# Sheet1.net
KiCad netlist of a schematic drawn in Altium Designer
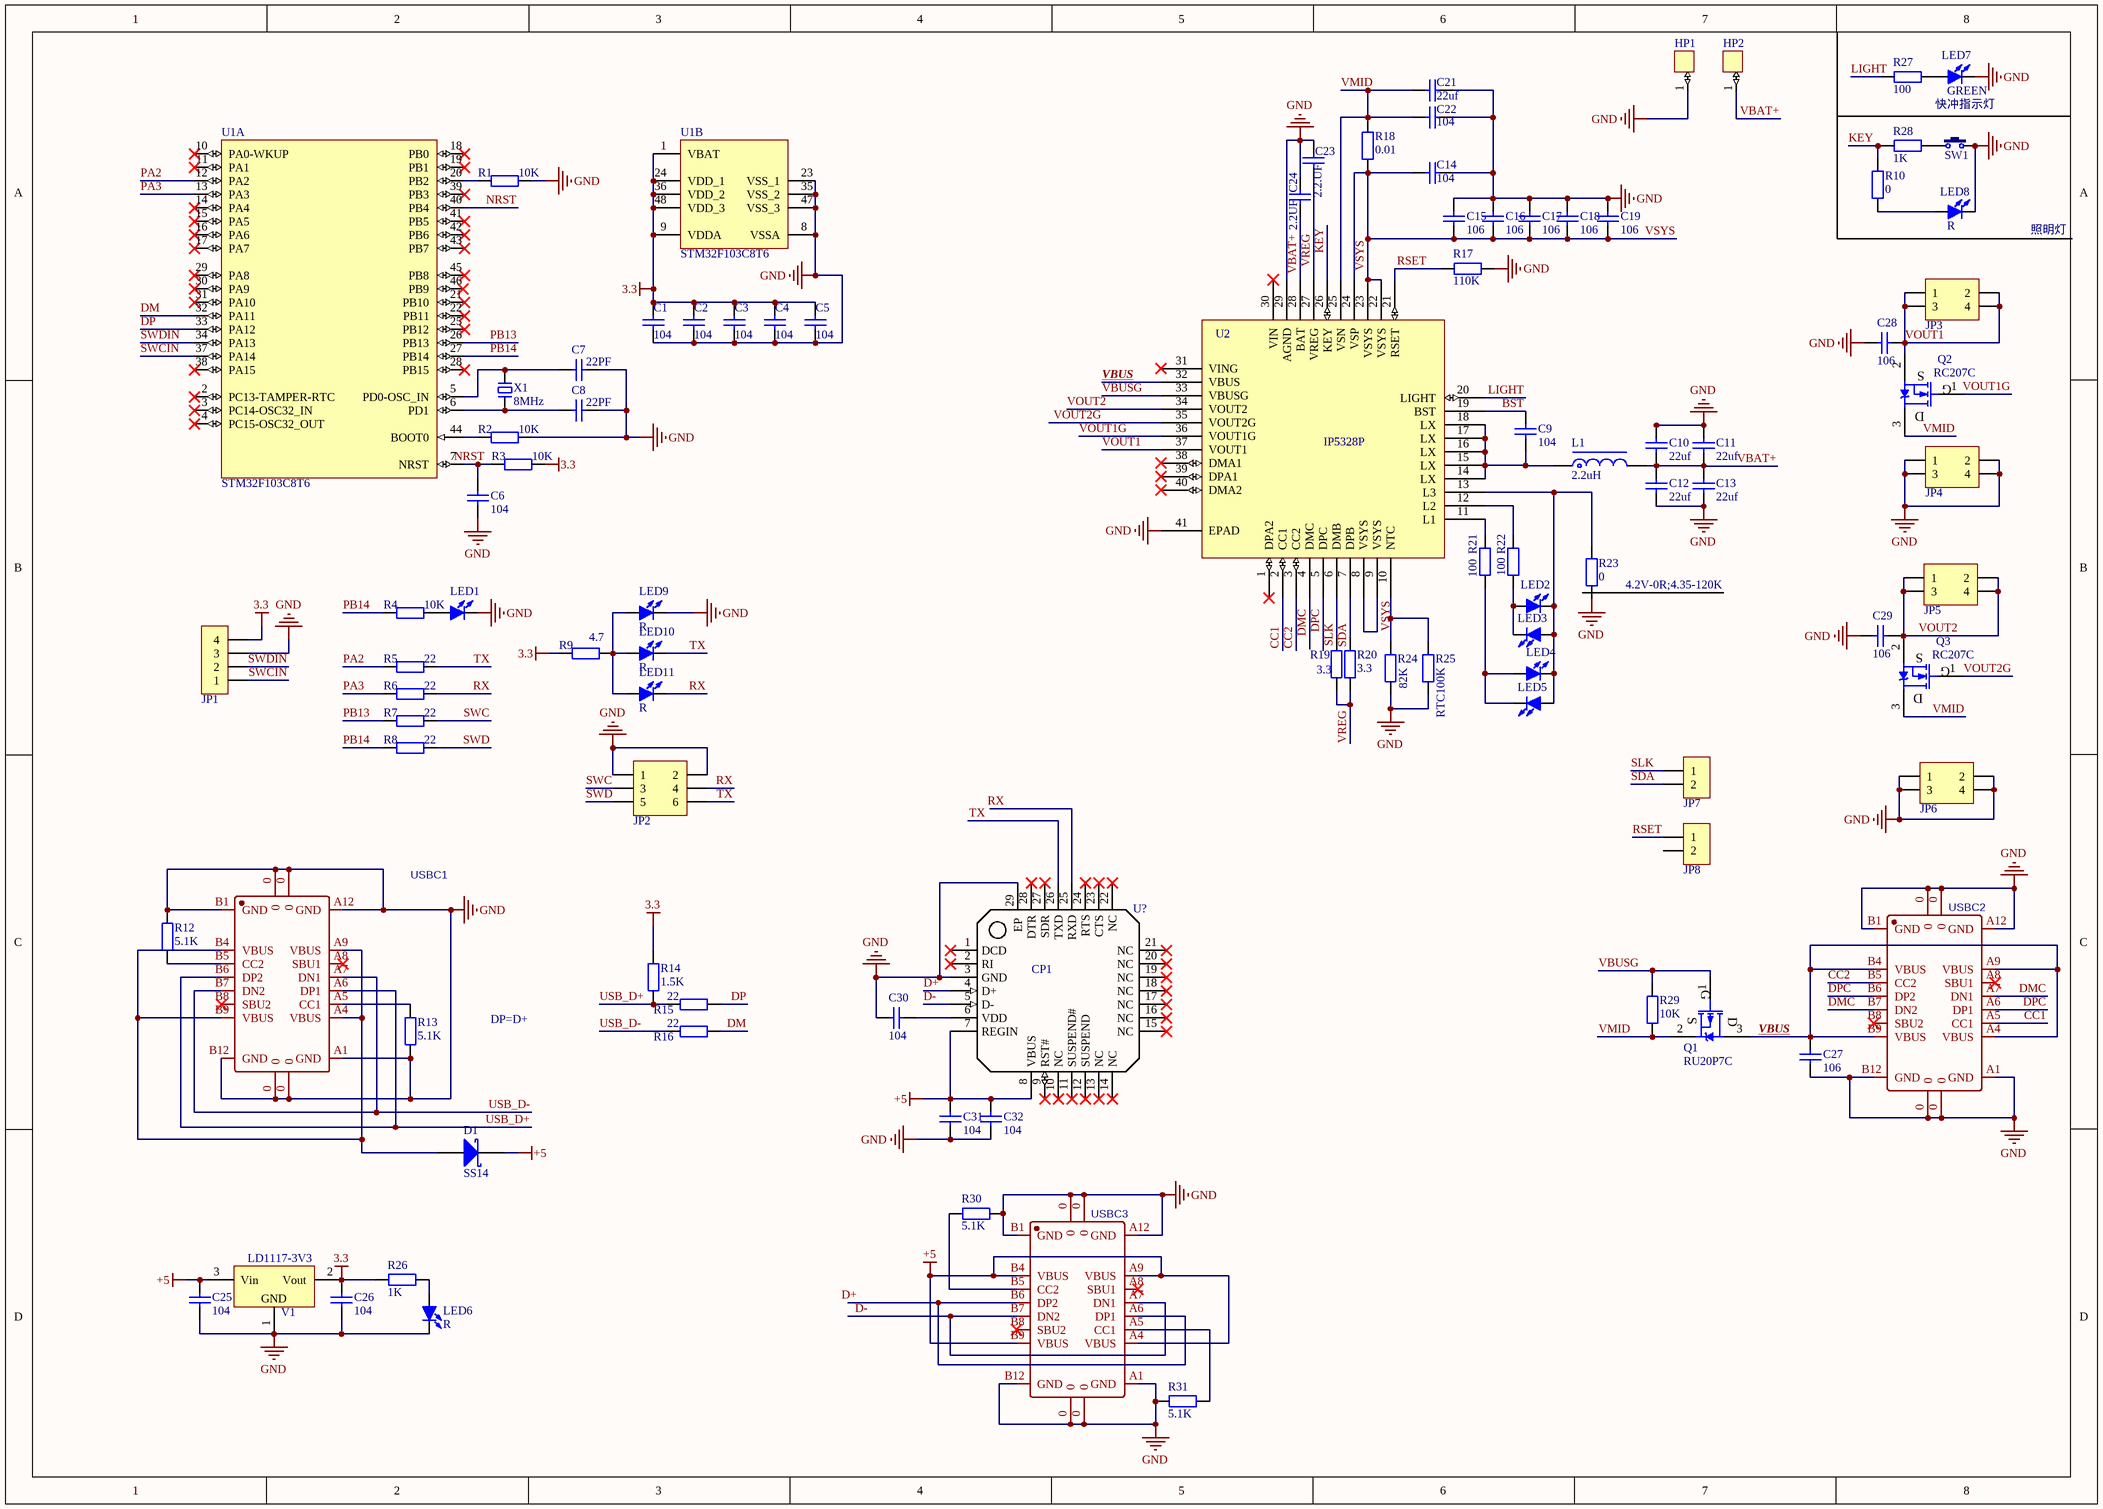
[diagram p0: Sheet1.SchDoc]

(export (version "E")
  (design (tool "Eeschema 10.0.6"))
  (components
    (comp (ref "C1")
      (value "104")
      (footprint "C 0603_L")
      (description "贴片电容")
      (libsource (lib "0.1 - 电阻-电容-电感") (part "C"))
    )
    (comp (ref "C2")
      (value "104")
      (footprint "C 0603_L")
      (description "贴片电容")
      (libsource (lib "0.1 - 电阻-电容-电感") (part "C"))
    )
    (comp (ref "C3")
      (value "104")
      (footprint "C 0603_L")
      (description "贴片电容")
      (libsource (lib "0.1 - 电阻-电容-电感") (part "C"))
    )
    (comp (ref "C4")
      (value "104")
      (footprint "C 0603_L")
      (description "贴片电容")
      (libsource (lib "0.1 - 电阻-电容-电感") (part "C"))
    )
    (comp (ref "C5")
      (value "104")
      (footprint "C 0603_L")
      (description "贴片电容")
      (libsource (lib "0.1 - 电阻-电容-电感") (part "C"))
    )
    (comp (ref "C6")
      (value "104")
      (footprint "C 0603_L")
      (description "贴片电容")
      (libsource (lib "0.1 - 电阻-电容-电感") (part "C"))
    )
    (comp (ref "C7")
      (value "22PF")
      (footprint "C 0603_L")
      (description "贴片电容")
      (libsource (lib "0.1 - 电阻-电容-电感") (part "C"))
    )
    (comp (ref "C8")
      (value "22PF")
      (footprint "C 0603_L")
      (description "贴片电容")
      (libsource (lib "0.1 - 电阻-电容-电感") (part "C"))
    )
    (comp (ref "C9")
      (value "104")
      (footprint "C 0603_L")
      (description "贴片电容")
      (libsource (lib "0.1 - 电阻-电容-电感") (part "C"))
    )
    (comp (ref "C10")
      (value "22uf")
      (footprint "C 0603_L")
      (description "贴片电容")
      (libsource (lib "0.1 - 电阻-电容-电感") (part "C"))
    )
    (comp (ref "C11")
      (value "22uf")
      (footprint "C 0603_L")
      (description "贴片电容")
      (libsource (lib "0.1 - 电阻-电容-电感") (part "C"))
    )
    (comp (ref "C12")
      (value "22uf")
      (footprint "C 0603_L")
      (description "贴片电容")
      (libsource (lib "0.1 - 电阻-电容-电感") (part "C"))
    )
    (comp (ref "C13")
      (value "22uf")
      (footprint "C 0603_L")
      (description "贴片电容")
      (libsource (lib "0.1 - 电阻-电容-电感") (part "C"))
    )
    (comp (ref "C14")
      (value "104")
      (footprint "C 0603_L")
      (description "贴片电容")
      (libsource (lib "0.1 - 电阻-电容-电感") (part "C"))
    )
    (comp (ref "C15")
      (value "106")
      (footprint "C 0603_L")
      (description "贴片电容")
      (libsource (lib "0.1 - 电阻-电容-电感") (part "C"))
    )
    (comp (ref "C16")
      (value "106")
      (footprint "C 0603_L")
      (description "贴片电容")
      (libsource (lib "0.1 - 电阻-电容-电感") (part "C"))
    )
    (comp (ref "C17")
      (value "106")
      (footprint "C 0603_L")
      (description "贴片电容")
      (libsource (lib "0.1 - 电阻-电容-电感") (part "C"))
    )
    (comp (ref "C18")
      (value "106")
      (footprint "C 0603_L")
      (description "贴片电容")
      (libsource (lib "0.1 - 电阻-电容-电感") (part "C"))
    )
    (comp (ref "C19")
      (value "106")
      (footprint "C 0603_L")
      (description "贴片电容")
      (libsource (lib "0.1 - 电阻-电容-电感") (part "C"))
    )
    (comp (ref "C21")
      (value "22uf")
      (footprint "C 0603_L")
      (description "贴片电容")
      (libsource (lib "0.1 - 电阻-电容-电感") (part "C"))
    )
    (comp (ref "C22")
      (value "104")
      (footprint "C 0603_L")
      (description "贴片电容")
      (libsource (lib "0.1 - 电阻-电容-电感") (part "C"))
    )
    (comp (ref "C23")
      (value "2.2.UF")
      (footprint "C 0603_L")
      (description "贴片电容")
      (libsource (lib "0.1 - 电阻-电容-电感") (part "C"))
    )
    (comp (ref "C24")
      (value "2.2UF")
      (footprint "C 0603_L")
      (description "贴片电容")
      (libsource (lib "0.1 - 电阻-电容-电感") (part "C"))
    )
    (comp (ref "C25")
      (value "104")
      (footprint "C 0603_L")
      (description "贴片电容")
      (libsource (lib "0.1 - 电阻-电容-电感") (part "C"))
    )
    (comp (ref "C26")
      (value "104")
      (footprint "C 0603_L")
      (description "贴片电容")
      (libsource (lib "0.1 - 电阻-电容-电感") (part "C"))
    )
    (comp (ref "C27")
      (value "106")
      (footprint "C 0603_L")
      (description "贴片电容")
      (libsource (lib "0.1 - 电阻-电容-电感") (part "C"))
    )
    (comp (ref "C28")
      (value "106")
      (footprint "C 0603_L")
      (description "贴片电容")
      (libsource (lib "0.1 - 电阻-电容-电感") (part "C"))
    )
    (comp (ref "C29")
      (value "106")
      (footprint "C 0603_L")
      (description "贴片电容")
      (libsource (lib "0.1 - 电阻-电容-电感") (part "C"))
    )
    (comp (ref "C30")
      (value "104")
      (footprint "C 0603_L")
      (description "贴片电容")
      (libsource (lib "0.1 - 电阻-电容-电感") (part "C"))
    )
    (comp (ref "C31")
      (value "104")
      (footprint "C 0603_L")
      (description "贴片电容")
      (libsource (lib "0.1 - 电阻-电容-电感") (part "C"))
    )
    (comp (ref "C32")
      (value "104")
      (footprint "C 0603_L")
      (description "贴片电容")
      (libsource (lib "0.1 - 电阻-电容-电感") (part "C"))
    )
    (comp (ref "CP1")
      (value "U?")
      (footprint "QFN28 5x5_N")
      (description "USB转TTL")
      (libsource (lib "1.0 - 常见芯片") (part "CP2102N"))
    )
    (comp (ref "D1")
      (value "SS14")
      (footprint "SOD-123")
      (description "肖特基二极管")
      (libsource (lib "0.2 - 二极管-整流桥") (part "SS14"))
    )
    (comp (ref "HP1")
      (value "~")
      (footprint "焊盘1.5X1.5")
      (libsource (lib "5.4 - 接插件-脚距2.54 (100mil) ") (part "HP?"))
    )
    (comp (ref "HP2")
      (value "~")
      (footprint "焊盘1.5X1.5")
      (libsource (lib "5.4 - 接插件-脚距2.54 (100mil) ") (part "HP?"))
    )
    (comp (ref "JP1")
      (value "HDR-1X4")
      (footprint "HDR2.54-LI-4P")
      (description "4P接插件")
      (libsource (lib "5.4 - 接插件-脚距2.54 (100mil) ") (part "Header 4"))
    )
    (comp (ref "JP2")
      (value "Header3X2")
      (footprint "HDR2.54-LI-2x3P")
      (description "3*2P接插件")
      (libsource (lib "5.4 - 接插件-脚距2.54 (100mil) ") (part "Header 3X2"))
    )
    (comp (ref "JP3")
      (value "Header2X2")
      (footprint "HDR2.54-LI-2x2P")
      (description "2*2P接插件")
      (libsource (lib "5.4 - 接插件-脚距2.54 (100mil) ") (part "Header 2X2"))
    )
    (comp (ref "JP4")
      (value "Header2X2")
      (footprint "HDR2.54-LI-2x2P")
      (description "2*2P接插件")
      (libsource (lib "5.4 - 接插件-脚距2.54 (100mil) ") (part "Header 2X2"))
    )
    (comp (ref "JP5")
      (value "Header2X2")
      (footprint "HDR2.54-LI-2x2P")
      (description "2*2P接插件")
      (libsource (lib "5.4 - 接插件-脚距2.54 (100mil) ") (part "Header 2X2"))
    )
    (comp (ref "JP6")
      (value "Header2X2")
      (footprint "HDR2.54-LI-2x2P")
      (description "2*2P接插件")
      (libsource (lib "5.4 - 接插件-脚距2.54 (100mil) ") (part "Header 2X2"))
    )
    (comp (ref "JP7")
      (value "HDR-1X2")
      (footprint "HDR2.54-LI-2P")
      (description "2P接插件")
      (libsource (lib "5.4 - 接插件-脚距2.54 (100mil) ") (part "Header 2"))
    )
    (comp (ref "JP8")
      (value "HDR-1X2")
      (footprint "HDR2.54-LI-2P")
      (description "2P接插件")
      (libsource (lib "5.4 - 接插件-脚距2.54 (100mil) ") (part "Header 2"))
    )
    (comp (ref "L1")
      (value "2.2uH")
      (footprint "CDRH73")
      (description "功率屏蔽电感")
      (libsource (lib "0.1 - 电阻-电容-电感") (part "L-CDRH"))
    )
    (comp (ref "LED1")
      (value "~")
      (footprint "LED 0603R")
      (description "贴片LED")
      (libsource (lib "0.3 - LED发光二极管") (part "LED-SMD"))
    )
    (comp (ref "LED2")
      (value "~")
      (footprint "LED 0603R")
      (description "贴片LED")
      (libsource (lib "0.3 - LED发光二极管") (part "LED-SMD"))
    )
    (comp (ref "LED3")
      (value "~")
      (footprint "LED 0603R")
      (description "贴片LED")
      (libsource (lib "0.3 - LED发光二极管") (part "LED-SMD"))
    )
    (comp (ref "LED4")
      (value "~")
      (footprint "LED 0603R")
      (description "贴片LED")
      (libsource (lib "0.3 - LED发光二极管") (part "LED-SMD"))
    )
    (comp (ref "LED5")
      (value "~")
      (footprint "LED 0603R")
      (description "贴片LED")
      (libsource (lib "0.3 - LED发光二极管") (part "LED-SMD"))
    )
    (comp (ref "LED6")
      (value "R")
      (footprint "LED 0603R")
      (description "贴片LED")
      (libsource (lib "0.3 - LED发光二极管") (part "LED-SMD"))
    )
    (comp (ref "LED7")
      (value "GREEN")
      (footprint "LED 0603R")
      (description "贴片LED")
      (libsource (lib "0.3 - LED发光二极管") (part "LED-SMD"))
    )
    (comp (ref "LED8")
      (value "R")
      (footprint "LED 5730-V")
      (description "贴片LED")
      (libsource (lib "0.3 - LED发光二极管") (part "LED-SMD"))
    )
    (comp (ref "LED9")
      (value "R")
      (footprint "LED 0603Y")
      (description "贴片LED")
      (libsource (lib "0.3 - LED发光二极管") (part "LED-SMD"))
    )
    (comp (ref "LED10")
      (value "R")
      (footprint "LED 0603Y")
      (description "贴片LED")
      (libsource (lib "0.3 - LED发光二极管") (part "LED-SMD"))
    )
    (comp (ref "LED11")
      (value "R")
      (footprint "LED 0603Y")
      (description "贴片LED")
      (libsource (lib "0.3 - LED发光二极管") (part "LED-SMD"))
    )
    (comp (ref "Q1")
      (value "RU20P7C")
      (footprint "SOT23-3N")
      (description "PMOS\r\nRds(on)<20m ohm      I>=4A")
      (libsource (lib "0.4 - 三极管-场效应管-可控硅") (part "RU20P7C"))
    )
    (comp (ref "Q2")
      (value "RC207C")
      (footprint "SOT23-3N")
      (description "NMOS \r\nRds(on)<20m ohm      I>=4A")
      (libsource (lib "0.4 - 三极管-场效应管-可控硅") (part "RU207C"))
    )
    (comp (ref "Q3")
      (value "RC207C")
      (footprint "SOT23-3N")
      (description "NMOS \r\nRds(on)<20m ohm      I>=4A")
      (libsource (lib "0.4 - 三极管-场效应管-可控硅") (part "RU207C"))
    )
    (comp (ref "R1")
      (value "10K")
      (footprint "R 0603_L")
      (description "贴片电阻")
      (libsource (lib "0.1 - 电阻-电容-电感") (part "R"))
    )
    (comp (ref "R2")
      (value "10K")
      (footprint "R 0603_L")
      (description "贴片电阻")
      (libsource (lib "0.1 - 电阻-电容-电感") (part "R"))
    )
    (comp (ref "R3")
      (value "10K")
      (footprint "R 0603_L")
      (description "贴片电阻")
      (libsource (lib "0.1 - 电阻-电容-电感") (part "R"))
    )
    (comp (ref "R4")
      (value "10K")
      (footprint "R 0603_L")
      (description "贴片电阻")
      (libsource (lib "0.1 - 电阻-电容-电感") (part "R"))
    )
    (comp (ref "R5")
      (value "22")
      (footprint "R 0603_L")
      (description "贴片电阻")
      (libsource (lib "0.1 - 电阻-电容-电感") (part "R"))
    )
    (comp (ref "R6")
      (value "22")
      (footprint "R 0603_L")
      (description "贴片电阻")
      (libsource (lib "0.1 - 电阻-电容-电感") (part "R"))
    )
    (comp (ref "R7")
      (value "22")
      (footprint "R 0603_L")
      (description "贴片电阻")
      (libsource (lib "0.1 - 电阻-电容-电感") (part "R"))
    )
    (comp (ref "R8")
      (value "22")
      (footprint "R 0603_L")
      (description "贴片电阻")
      (libsource (lib "0.1 - 电阻-电容-电感") (part "R"))
    )
    (comp (ref "R9")
      (value "4.7")
      (footprint "R 0603_L")
      (description "贴片电阻")
      (libsource (lib "0.1 - 电阻-电容-电感") (part "R"))
    )
    (comp (ref "R10")
      (value "0")
      (footprint "R 0603_L")
      (description "贴片电阻")
      (libsource (lib "0.1 - 电阻-电容-电感") (part "R"))
    )
    (comp (ref "R12")
      (value "5.1K")
      (footprint "R 0603_L")
      (description "贴片电阻")
      (libsource (lib "0.1 - 电阻-电容-电感") (part "R"))
    )
    (comp (ref "R13")
      (value "5.1K")
      (footprint "R 0603_L")
      (description "贴片电阻")
      (libsource (lib "0.1 - 电阻-电容-电感") (part "R"))
    )
    (comp (ref "R14")
      (value "1.5K")
      (footprint "R 0603_L")
      (description "贴片电阻")
      (libsource (lib "0.1 - 电阻-电容-电感") (part "R"))
    )
    (comp (ref "R15")
      (value "22")
      (footprint "R 0603_L")
      (description "贴片电阻")
      (libsource (lib "0.1 - 电阻-电容-电感") (part "R"))
    )
    (comp (ref "R16")
      (value "22")
      (footprint "R 0603_L")
      (description "贴片电阻")
      (libsource (lib "0.1 - 电阻-电容-电感") (part "R"))
    )
    (comp (ref "R17")
      (value "110K")
      (footprint "R 0603_L")
      (description "贴片电阻")
      (libsource (lib "0.1 - 电阻-电容-电感") (part "R"))
    )
    (comp (ref "R18")
      (value "0.01")
      (footprint "R 1206_L")
      (description "贴片电阻")
      (libsource (lib "0.1 - 电阻-电容-电感") (part "R"))
    )
    (comp (ref "R19")
      (value "3.3")
      (footprint "R 0603_L")
      (description "贴片电阻")
      (libsource (lib "0.1 - 电阻-电容-电感") (part "R"))
    )
    (comp (ref "R20")
      (value "3.3")
      (footprint "R 0603_L")
      (description "贴片电阻")
      (libsource (lib "0.1 - 电阻-电容-电感") (part "R"))
    )
    (comp (ref "R21")
      (value "100")
      (footprint "R 0603_L")
      (description "贴片电阻")
      (libsource (lib "0.1 - 电阻-电容-电感") (part "R"))
    )
    (comp (ref "R22")
      (value "100")
      (footprint "R 0603_L")
      (description "贴片电阻")
      (libsource (lib "0.1 - 电阻-电容-电感") (part "R"))
    )
    (comp (ref "R23")
      (value "0")
      (footprint "R 0603_L")
      (description "贴片电阻")
      (libsource (lib "0.1 - 电阻-电容-电感") (part "R"))
    )
    (comp (ref "R24")
      (value "82K")
      (footprint "R 0603_L")
      (description "贴片电阻")
      (libsource (lib "0.1 - 电阻-电容-电感") (part "R"))
    )
    (comp (ref "R25")
      (value "RTC100K")
      (footprint "R 0603_L")
      (description "贴片电阻")
      (libsource (lib "0.1 - 电阻-电容-电感") (part "R"))
    )
    (comp (ref "R26")
      (value "1K")
      (footprint "R 0603_L")
      (description "贴片电阻")
      (libsource (lib "0.1 - 电阻-电容-电感") (part "R"))
    )
    (comp (ref "R27")
      (value "100")
      (footprint "R 0603_L")
      (description "贴片电阻")
      (libsource (lib "0.1 - 电阻-电容-电感") (part "R"))
    )
    (comp (ref "R28")
      (value "1K")
      (footprint "R 0603_L")
      (description "贴片电阻")
      (libsource (lib "0.1 - 电阻-电容-电感") (part "R"))
    )
    (comp (ref "R29")
      (value "10K")
      (footprint "R 0603_L")
      (description "贴片电阻")
      (libsource (lib "0.1 - 电阻-电容-电感") (part "R"))
    )
    (comp (ref "R30")
      (value "5.1K")
      (footprint "R 0603_L")
      (description "贴片电阻")
      (libsource (lib "0.1 - 电阻-电容-电感") (part "R"))
    )
    (comp (ref "R31")
      (value "5.1K")
      (footprint "R 0603_L")
      (description "贴片电阻")
      (libsource (lib "0.1 - 电阻-电容-电感") (part "R"))
    )
    (comp (ref "SW1")
      (value "3x6x5")
      (footprint "TSW 3*6*4.3-S-W")
      (description "3x6轻触开关")
      (libsource (lib "0.7 - 常用按键-开关-蜂鸣器-电池") (part "TSW 3x6"))
    )
    (comp (ref "U1")
      (value "STM32F103C8T6")
      (footprint "LQFP48_N")
      (libsource (lib "2.4 - STM32 F1系列单片机") (part "STM32F103C8T6"))
    )
    (comp (ref "U2")
      (value "IP5328P")
      (footprint "QFN40 6X6_N")
      (libsource (lib "1.1 - 电源类芯片") (part "IP5328P"))
    )
    (comp (ref "USBC1")
      (value "TYPE-C 2.0 -16P")
      (footprint "USB-C-SMD_TYPE-C-USB-5")
      (description "USB2.0 Type-C 母座 16Pin")
      (libsource (lib "0.8 - 以太网-音频-USB插座") (part "USB2.0 Type-C 16Pin母座"))
    )
    (comp (ref "USBC2")
      (value "TYPE-C 2.0 -16P")
      (footprint "USB-C-SMD_TYPE-C-USB-5")
      (description "USB2.0 Type-C 母座 16Pin")
      (libsource (lib "0.8 - 以太网-音频-USB插座") (part "USB2.0 Type-C 16Pin母座"))
    )
    (comp (ref "USBC3")
      (value "TYPE-C 2.0 -16P")
      (footprint "USB-C-SMD_TYPE-C-USB-5")
      (description "USB2.0 Type-C 母座 16Pin")
      (libsource (lib "0.8 - 以太网-音频-USB插座") (part "USB2.0 Type-C 16Pin母座"))
    )
    (comp (ref "V1")
      (value "LD1117-3V3")
      (footprint "SOT89_L")
      (description "三端稳压芯片")
      (libsource (lib "1.1 - 电源类芯片") (part "LD1117"))
    )
    (comp (ref "X1")
      (value "8MHz")
      (footprint "OSC 5032-2P")
      (description "2脚无源脚晶振")
      (libsource (lib "0.5 - 保险丝-晶振-光耦") (part "XTAL-2P"))
    )
  )
  (nets
    (net (code "1") (name "+5") (class "Default")
      (node (ref "C25") (pin "2") (pinfunction "2_2") (pintype "passive"))
      (node (ref "C31") (pin "1") (pinfunction "1_1") (pintype "passive"))
      (node (ref "C32") (pin "1") (pinfunction "1_1") (pintype "passive"))
      (node (ref "CP1") (pin "7") (pinfunction "REGIN_7") (pintype "power_in"))
      (node (ref "CP1") (pin "8") (pinfunction "VBUS_8") (pintype "power_in"))
      (node (ref "D1") (pin "2") (pinfunction "K_2") (pintype "passive"))
      (node (ref "USBC3") (pin "A4") (pinfunction "VBUS_A4") (pintype "passive"))
      (node (ref "USBC3") (pin "A9") (pinfunction "VBUS_A9") (pintype "passive"))
      (node (ref "USBC3") (pin "B4") (pinfunction "VBUS_B4") (pintype "passive"))
      (node (ref "USBC3") (pin "B9") (pinfunction "VBUS_B9") (pintype "passive"))
      (node (ref "V1") (pin "3") (pinfunction "Vin_3") (pintype "passive"))
    )
    (net (code "2") (name "/BST") (class "Default")
      (node (ref "C9") (pin "2") (pinfunction "2_2") (pintype "passive"))
      (node (ref "U2") (pin "19") (pinfunction "BST_19") (pintype "passive"))
    )
    (net (code "3") (name "/CC1") (class "Default")
      (node (ref "U2") (pin "2") (pinfunction "CC1_2") (pintype "bidirectional"))
      (node (ref "USBC2") (pin "A5") (pinfunction "CC1_A5") (pintype "passive"))
    )
    (net (code "4") (name "/CC2") (class "Default")
      (node (ref "U2") (pin "3") (pinfunction "CC2_3") (pintype "bidirectional"))
      (node (ref "USBC2") (pin "B5") (pinfunction "CC2_B5") (pintype "passive"))
    )
    (net (code "5") (name "/D+") (class "Default")
      (node (ref "CP1") (pin "4") (pinfunction "D+_4") (pintype "input"))
      (node (ref "USBC3") (pin "A6") (pinfunction "DP1_A6") (pintype "passive"))
      (node (ref "USBC3") (pin "B6") (pinfunction "DP2_B6") (pintype "passive"))
    )
    (net (code "6") (name "/D-") (class "Default")
      (node (ref "CP1") (pin "5") (pinfunction "D-_5") (pintype "input"))
      (node (ref "USBC3") (pin "A7") (pinfunction "DN1_A7") (pintype "passive"))
      (node (ref "USBC3") (pin "B7") (pinfunction "DN2_B7") (pintype "passive"))
    )
    (net (code "7") (name "/DM") (class "Default")
      (node (ref "R16") (pin "2") (pinfunction "2_2") (pintype "passive"))
      (node (ref "U1") (pin "32") (pinfunction "PA11_32") (pintype "bidirectional"))
    )
    (net (code "8") (name "/DMC") (class "Default")
      (node (ref "U2") (pin "4") (pinfunction "DMC_4") (pintype "passive"))
      (node (ref "USBC2") (pin "A7") (pinfunction "DN1_A7") (pintype "passive"))
      (node (ref "USBC2") (pin "B7") (pinfunction "DN2_B7") (pintype "passive"))
    )
    (net (code "9") (name "/DP") (class "Default")
      (node (ref "R15") (pin "2") (pinfunction "2_2") (pintype "passive"))
      (node (ref "U1") (pin "33") (pinfunction "PA12_33") (pintype "bidirectional"))
    )
    (net (code "10") (name "/DPC") (class "Default")
      (node (ref "U2") (pin "5") (pinfunction "DPC_5") (pintype "passive"))
      (node (ref "USBC2") (pin "A6") (pinfunction "DP1_A6") (pintype "passive"))
      (node (ref "USBC2") (pin "B6") (pinfunction "DP2_B6") (pintype "passive"))
    )
    (net (code "11") (name "/KEY") (class "Default")
      (node (ref "R10") (pin "2") (pinfunction "2_2") (pintype "passive"))
      (node (ref "R28") (pin "1") (pinfunction "1_1") (pintype "passive"))
      (node (ref "U2") (pin "26") (pinfunction "KEY_26") (pintype "bidirectional"))
    )
    (net (code "12") (name "/LIGHT") (class "Default")
      (node (ref "R27") (pin "1") (pinfunction "1_1") (pintype "passive"))
      (node (ref "U2") (pin "20") (pinfunction "LIGHT_20") (pintype "bidirectional"))
    )
    (net (code "13") (name "/NRST") (class "Default")
      (node (ref "C6") (pin "2") (pinfunction "2_2") (pintype "passive"))
      (node (ref "R3") (pin "1") (pinfunction "1_1") (pintype "passive"))
      (node (ref "U1") (pin "40") (pinfunction "PB4_40") (pintype "bidirectional"))
      (node (ref "U1") (pin "7") (pinfunction "NRST_7") (pintype "bidirectional"))
    )
    (net (code "14") (name "/PA2") (class "Default")
      (node (ref "R5") (pin "1") (pinfunction "1_1") (pintype "passive"))
      (node (ref "U1") (pin "12") (pinfunction "PA2_12") (pintype "bidirectional"))
    )
    (net (code "15") (name "/PA3") (class "Default")
      (node (ref "R6") (pin "1") (pinfunction "1_1") (pintype "passive"))
      (node (ref "U1") (pin "13") (pinfunction "PA3_13") (pintype "bidirectional"))
    )
    (net (code "16") (name "/PB13") (class "Default")
      (node (ref "R7") (pin "1") (pinfunction "1_1") (pintype "passive"))
      (node (ref "U1") (pin "26") (pinfunction "PB13_26") (pintype "bidirectional"))
    )
    (net (code "17") (name "/PB14") (class "Default")
      (node (ref "R4") (pin "1") (pinfunction "1_1") (pintype "passive"))
      (node (ref "R8") (pin "1") (pinfunction "1_1") (pintype "passive"))
      (node (ref "U1") (pin "27") (pinfunction "PB14_27") (pintype "bidirectional"))
    )
    (net (code "18") (name "/RSET") (class "Default")
      (node (ref "JP8") (pin "1") (pinfunction "1_1") (pintype "passive"))
      (node (ref "R17") (pin "1") (pinfunction "1_1") (pintype "passive"))
      (node (ref "U2") (pin "21") (pinfunction "RSET_21") (pintype "bidirectional"))
    )
    (net (code "19") (name "/RX") (class "Default")
      (node (ref "CP1") (pin "25") (pinfunction "RXD_25") (pintype "passive"))
      (node (ref "JP2") (pin "4") (pinfunction "4_4") (pintype "passive"))
      (node (ref "LED11") (pin "2") (pinfunction "K_2") (pintype "passive"))
      (node (ref "R6") (pin "2") (pinfunction "2_2") (pintype "passive"))
    )
    (net (code "20") (name "/SDA") (class "Default")
      (node (ref "JP7") (pin "2") (pinfunction "2_2") (pintype "passive"))
      (node (ref "R20") (pin "2") (pinfunction "2_2") (pintype "passive"))
      (node (ref "U2") (pin "7") (pinfunction "DPB_7") (pintype "passive"))
    )
    (net (code "21") (name "/SLK") (class "Default")
      (node (ref "JP7") (pin "1") (pinfunction "1_1") (pintype "passive"))
      (node (ref "R19") (pin "1") (pinfunction "1_1") (pintype "passive"))
      (node (ref "U2") (pin "6") (pinfunction "DMB_6") (pintype "passive"))
    )
    (net (code "22") (name "/SWC") (class "Default")
      (node (ref "JP2") (pin "3") (pinfunction "3_3") (pintype "passive"))
      (node (ref "R7") (pin "2") (pinfunction "2_2") (pintype "passive"))
    )
    (net (code "23") (name "/SWCIN") (class "Default")
      (node (ref "JP1") (pin "1") (pinfunction "1_1") (pintype "passive"))
      (node (ref "U1") (pin "37") (pinfunction "PA14_37") (pintype "bidirectional"))
    )
    (net (code "24") (name "/SWD") (class "Default")
      (node (ref "JP2") (pin "5") (pinfunction "5_5") (pintype "passive"))
      (node (ref "R8") (pin "2") (pinfunction "2_2") (pintype "passive"))
    )
    (net (code "25") (name "/SWDIN") (class "Default")
      (node (ref "JP1") (pin "2") (pinfunction "2_2") (pintype "passive"))
      (node (ref "U1") (pin "34") (pinfunction "PA13_34") (pintype "bidirectional"))
    )
    (net (code "26") (name "/TX") (class "Default")
      (node (ref "CP1") (pin "26") (pinfunction "TXD_26") (pintype "passive"))
      (node (ref "JP2") (pin "6") (pinfunction "6_6") (pintype "passive"))
      (node (ref "LED10") (pin "2") (pinfunction "K_2") (pintype "passive"))
      (node (ref "R5") (pin "2") (pinfunction "2_2") (pintype "passive"))
    )
    (net (code "27") (name "/USB_D+") (class "Default")
      (node (ref "R14") (pin "1") (pinfunction "1_1") (pintype "passive"))
      (node (ref "R15") (pin "1") (pinfunction "1_1") (pintype "passive"))
      (node (ref "USBC1") (pin "A6") (pinfunction "DP1_A6") (pintype "passive"))
      (node (ref "USBC1") (pin "B6") (pinfunction "DP2_B6") (pintype "passive"))
    )
    (net (code "28") (name "/USB_D-") (class "Default")
      (node (ref "R16") (pin "1") (pinfunction "1_1") (pintype "passive"))
      (node (ref "USBC1") (pin "A7") (pinfunction "DN1_A7") (pintype "passive"))
      (node (ref "USBC1") (pin "B7") (pinfunction "DN2_B7") (pintype "passive"))
    )
    (net (code "29") (name "/VBAT+") (class "Default")
      (node (ref "C10") (pin "1") (pinfunction "1_1") (pintype "passive"))
      (node (ref "C11") (pin "1") (pinfunction "1_1") (pintype "passive"))
      (node (ref "C12") (pin "2") (pinfunction "2_2") (pintype "passive"))
      (node (ref "C13") (pin "2") (pinfunction "2_2") (pintype "passive"))
      (node (ref "C24") (pin "1") (pinfunction "1_1") (pintype "passive"))
      (node (ref "HP2") (pin "1") (pintype "bidirectional"))
      (node (ref "L1") (pin "2") (pinfunction "2_2") (pintype "passive"))
      (node (ref "U2") (pin "28") (pinfunction "BAT_28") (pintype "power_in"))
    )
    (net (code "30") (name "/VBUS") (class "Default")
      (node (ref "C27") (pin "2") (pinfunction "2_2") (pintype "passive"))
      (node (ref "Q1") (pin "3") (pinfunction "D_3") (pintype "passive"))
      (node (ref "U2") (pin "32") (pinfunction "VBUS_32") (pintype "power_in"))
      (node (ref "USBC2") (pin "A4") (pinfunction "VBUS_A4") (pintype "passive"))
      (node (ref "USBC2") (pin "A9") (pinfunction "VBUS_A9") (pintype "passive"))
      (node (ref "USBC2") (pin "B4") (pinfunction "VBUS_B4") (pintype "passive"))
      (node (ref "USBC2") (pin "B9") (pinfunction "VBUS_B9") (pintype "passive"))
    )
    (net (code "31") (name "/VBUSG") (class "Default")
      (node (ref "Q1") (pin "1") (pinfunction "G_1") (pintype "passive"))
      (node (ref "R29") (pin "2") (pinfunction "2_2") (pintype "passive"))
      (node (ref "U2") (pin "33") (pinfunction "VBUSG_33") (pintype "power_in"))
    )
    (net (code "32") (name "/VMID") (class "Default")
      (node (ref "C21") (pin "2") (pinfunction "2_2") (pintype "passive"))
      (node (ref "C22") (pin "2") (pinfunction "2_2") (pintype "passive"))
      (node (ref "Q1") (pin "2") (pinfunction "S_2") (pintype "passive"))
      (node (ref "Q2") (pin "3") (pinfunction "D_3") (pintype "passive"))
      (node (ref "Q3") (pin "3") (pinfunction "D_3") (pintype "passive"))
      (node (ref "R18") (pin "1") (pinfunction "1_1") (pintype "passive"))
      (node (ref "R29") (pin "1") (pinfunction "1_1") (pintype "passive"))
      (node (ref "U2") (pin "25") (pinfunction "VSN_25") (pintype "passive"))
    )
    (net (code "33") (name "/VOUT1") (class "Default")
      (node (ref "C28") (pin "1") (pinfunction "1_1") (pintype "passive"))
      (node (ref "JP3") (pin "1") (pinfunction "1_1") (pintype "passive"))
      (node (ref "JP3") (pin "2") (pinfunction "2_2") (pintype "passive"))
      (node (ref "JP3") (pin "3") (pinfunction "3_3") (pintype "passive"))
      (node (ref "JP3") (pin "4") (pinfunction "4_4") (pintype "passive"))
      (node (ref "Q2") (pin "2") (pinfunction "S_2") (pintype "passive"))
      (node (ref "U2") (pin "37") (pinfunction "VOUT1_37") (pintype "power_in"))
    )
    (net (code "34") (name "/VOUT1G") (class "Default")
      (node (ref "Q2") (pin "1") (pinfunction "G_1") (pintype "passive"))
      (node (ref "U2") (pin "36") (pinfunction "VOUT1G_36") (pintype "power_in"))
    )
    (net (code "35") (name "/VOUT2") (class "Default")
      (node (ref "C29") (pin "2") (pinfunction "2_2") (pintype "passive"))
      (node (ref "JP5") (pin "1") (pinfunction "1_1") (pintype "passive"))
      (node (ref "JP5") (pin "2") (pinfunction "2_2") (pintype "passive"))
      (node (ref "JP5") (pin "3") (pinfunction "3_3") (pintype "passive"))
      (node (ref "JP5") (pin "4") (pinfunction "4_4") (pintype "passive"))
      (node (ref "Q3") (pin "2") (pinfunction "S_2") (pintype "passive"))
      (node (ref "U2") (pin "34") (pinfunction "VOUT2_34") (pintype "power_in"))
    )
    (net (code "36") (name "/VOUT2G") (class "Default")
      (node (ref "Q3") (pin "1") (pinfunction "G_1") (pintype "passive"))
      (node (ref "U2") (pin "35") (pinfunction "VOUT2G_35") (pintype "power_in"))
    )
    (net (code "37") (name "/VREG") (class "Default")
      (node (ref "C23") (pin "1") (pinfunction "1_1") (pintype "passive"))
      (node (ref "R19") (pin "2") (pinfunction "2_2") (pintype "passive"))
      (node (ref "R20") (pin "1") (pinfunction "1_1") (pintype "passive"))
      (node (ref "U2") (pin "27") (pinfunction "VREG_27") (pintype "passive"))
    )
    (net (code "38") (name "/VSYS") (class "Default")
      (node (ref "C14") (pin "2") (pinfunction "2_2") (pintype "passive"))
      (node (ref "C15") (pin "1") (pinfunction "1_1") (pintype "passive"))
      (node (ref "C16") (pin "1") (pinfunction "1_1") (pintype "passive"))
      (node (ref "C17") (pin "1") (pinfunction "1_1") (pintype "passive"))
      (node (ref "C18") (pin "1") (pinfunction "1_1") (pintype "passive"))
      (node (ref "C19") (pin "1") (pinfunction "1_1") (pintype "passive"))
      (node (ref "R18") (pin "2") (pinfunction "2_2") (pintype "passive"))
      (node (ref "U2") (pin "22") (pinfunction "VSYS_22") (pintype "passive"))
      (node (ref "U2") (pin "23") (pinfunction "VSYS_23") (pintype "passive"))
      (node (ref "U2") (pin "24") (pinfunction "VSP_24") (pintype "passive"))
      (node (ref "U2") (pin "8") (pinfunction "VSYS_8") (pintype "passive"))
      (node (ref "U2") (pin "9") (pinfunction "VSYS_9") (pintype "passive"))
    )
    (net (code "39") (name "3.3") (class "Default")
      (node (ref "C1") (pin "2") (pinfunction "2_2") (pintype "passive"))
      (node (ref "C2") (pin "2") (pinfunction "2_2") (pintype "passive"))
      (node (ref "C26") (pin "2") (pinfunction "2_2") (pintype "passive"))
      (node (ref "C3") (pin "2") (pinfunction "2_2") (pintype "passive"))
      (node (ref "C4") (pin "2") (pinfunction "2_2") (pintype "passive"))
      (node (ref "C5") (pin "2") (pinfunction "2_2") (pintype "passive"))
      (node (ref "JP1") (pin "4") (pinfunction "4_4") (pintype "passive"))
      (node (ref "R14") (pin "2") (pinfunction "2_2") (pintype "passive"))
      (node (ref "R26") (pin "1") (pinfunction "1_1") (pintype "passive"))
      (node (ref "R3") (pin "2") (pinfunction "2_2") (pintype "passive"))
      (node (ref "R9") (pin "1") (pinfunction "1_1") (pintype "passive"))
      (node (ref "U1") (pin "1") (pinfunction "VBAT_1") (pintype "power_in"))
      (node (ref "U1") (pin "24") (pinfunction "VDD_1_24") (pintype "power_in"))
      (node (ref "U1") (pin "36") (pinfunction "VDD_2_36") (pintype "power_in"))
      (node (ref "U1") (pin "48") (pinfunction "VDD_3_48") (pintype "power_in"))
      (node (ref "U1") (pin "9") (pinfunction "VDDA_9") (pintype "power_in"))
      (node (ref "V1") (pin "2") (pinfunction "Vout_2") (pintype "passive"))
    )
    (net (code "40") (name "GND") (class "Default")
      (node (ref "C1") (pin "1") (pinfunction "1_1") (pintype "passive"))
      (node (ref "C10") (pin "2") (pinfunction "2_2") (pintype "passive"))
      (node (ref "C11") (pin "2") (pinfunction "2_2") (pintype "passive"))
      (node (ref "C12") (pin "1") (pinfunction "1_1") (pintype "passive"))
      (node (ref "C13") (pin "1") (pinfunction "1_1") (pintype "passive"))
      (node (ref "C14") (pin "1") (pinfunction "1_1") (pintype "passive"))
      (node (ref "C15") (pin "2") (pinfunction "2_2") (pintype "passive"))
      (node (ref "C16") (pin "2") (pinfunction "2_2") (pintype "passive"))
      (node (ref "C17") (pin "2") (pinfunction "2_2") (pintype "passive"))
      (node (ref "C18") (pin "2") (pinfunction "2_2") (pintype "passive"))
      (node (ref "C19") (pin "2") (pinfunction "2_2") (pintype "passive"))
      (node (ref "C2") (pin "1") (pinfunction "1_1") (pintype "passive"))
      (node (ref "C21") (pin "1") (pinfunction "1_1") (pintype "passive"))
      (node (ref "C22") (pin "1") (pinfunction "1_1") (pintype "passive"))
      (node (ref "C23") (pin "2") (pinfunction "2_2") (pintype "passive"))
      (node (ref "C24") (pin "2") (pinfunction "2_2") (pintype "passive"))
      (node (ref "C25") (pin "1") (pinfunction "1_1") (pintype "passive"))
      (node (ref "C26") (pin "1") (pinfunction "1_1") (pintype "passive"))
      (node (ref "C27") (pin "1") (pinfunction "1_1") (pintype "passive"))
      (node (ref "C28") (pin "2") (pinfunction "2_2") (pintype "passive"))
      (node (ref "C29") (pin "1") (pinfunction "1_1") (pintype "passive"))
      (node (ref "C3") (pin "1") (pinfunction "1_1") (pintype "passive"))
      (node (ref "C30") (pin "2") (pinfunction "2_2") (pintype "passive"))
      (node (ref "C31") (pin "2") (pinfunction "2_2") (pintype "passive"))
      (node (ref "C32") (pin "2") (pinfunction "2_2") (pintype "passive"))
      (node (ref "C4") (pin "1") (pinfunction "1_1") (pintype "passive"))
      (node (ref "C5") (pin "1") (pinfunction "1_1") (pintype "passive"))
      (node (ref "C6") (pin "1") (pinfunction "1_1") (pintype "passive"))
      (node (ref "C7") (pin "1") (pinfunction "1_1") (pintype "passive"))
      (node (ref "C8") (pin "1") (pinfunction "1_1") (pintype "passive"))
      (node (ref "CP1") (pin "29") (pinfunction "EP_29") (pintype "passive"))
      (node (ref "CP1") (pin "3") (pinfunction "GND_3") (pintype "passive"))
      (node (ref "HP1") (pin "1") (pintype "bidirectional"))
      (node (ref "JP1") (pin "3") (pinfunction "3_3") (pintype "passive"))
      (node (ref "JP2") (pin "1") (pinfunction "1_1") (pintype "passive"))
      (node (ref "JP2") (pin "2") (pinfunction "2_2") (pintype "passive"))
      (node (ref "JP4") (pin "1") (pinfunction "1_1") (pintype "passive"))
      (node (ref "JP4") (pin "2") (pinfunction "2_2") (pintype "passive"))
      (node (ref "JP4") (pin "3") (pinfunction "3_3") (pintype "passive"))
      (node (ref "JP4") (pin "4") (pinfunction "4_4") (pintype "passive"))
      (node (ref "JP6") (pin "1") (pinfunction "1_1") (pintype "passive"))
      (node (ref "JP6") (pin "2") (pinfunction "2_2") (pintype "passive"))
      (node (ref "JP6") (pin "3") (pinfunction "3_3") (pintype "passive"))
      (node (ref "JP6") (pin "4") (pinfunction "4_4") (pintype "passive"))
      (node (ref "LED1") (pin "2") (pinfunction "K_2") (pintype "passive"))
      (node (ref "LED6") (pin "2") (pinfunction "K_2") (pintype "passive"))
      (node (ref "LED7") (pin "2") (pinfunction "K_2") (pintype "passive"))
      (node (ref "LED8") (pin "2") (pinfunction "K_2") (pintype "passive"))
      (node (ref "LED9") (pin "2") (pinfunction "K_2") (pintype "passive"))
      (node (ref "R1") (pin "2") (pinfunction "2_2") (pintype "passive"))
      (node (ref "R12") (pin "2") (pinfunction "2_2") (pintype "passive"))
      (node (ref "R13") (pin "1") (pinfunction "1_1") (pintype "passive"))
      (node (ref "R17") (pin "2") (pinfunction "2_2") (pintype "passive"))
      (node (ref "R2") (pin "2") (pinfunction "2_2") (pintype "passive"))
      (node (ref "R23") (pin "1") (pinfunction "1_1") (pintype "passive"))
      (node (ref "R24") (pin "2") (pinfunction "2_2") (pintype "passive"))
      (node (ref "R25") (pin "2") (pinfunction "2_2") (pintype "passive"))
      (node (ref "R30") (pin "2") (pinfunction "2_2") (pintype "passive"))
      (node (ref "R31") (pin "1") (pinfunction "1_1") (pintype "passive"))
      (node (ref "SW1") (pin "2") (pinfunction "2_2") (pintype "passive"))
      (node (ref "U1") (pin "23") (pinfunction "VSS_1_23") (pintype "power_in"))
      (node (ref "U1") (pin "35") (pinfunction "VSS_2_35") (pintype "power_in"))
      (node (ref "U1") (pin "47") (pinfunction "VSS_3_47") (pintype "power_in"))
      (node (ref "U1") (pin "8") (pinfunction "VSSA_8") (pintype "power_in"))
      (node (ref "U2") (pin "29") (pinfunction "AGND_29") (pintype "power_in"))
      (node (ref "U2") (pin "41") (pinfunction "EPAD_41") (pintype "power_in"))
      (node (ref "USBC1") (pin "0") (pinfunction "0_0") (pintype "passive"))
      (node (ref "USBC1") (pin "A1") (pinfunction "GND_A1") (pintype "passive"))
      (node (ref "USBC1") (pin "A12") (pinfunction "GND_A12") (pintype "passive"))
      (node (ref "USBC1") (pin "B1") (pinfunction "GND_B1") (pintype "passive"))
      (node (ref "USBC1") (pin "B12") (pinfunction "GND_B12") (pintype "passive"))
      (node (ref "USBC2") (pin "0") (pinfunction "0_0") (pintype "passive"))
      (node (ref "USBC2") (pin "A1") (pinfunction "GND_A1") (pintype "passive"))
      (node (ref "USBC2") (pin "A12") (pinfunction "GND_A12") (pintype "passive"))
      (node (ref "USBC2") (pin "B1") (pinfunction "GND_B1") (pintype "passive"))
      (node (ref "USBC2") (pin "B12") (pinfunction "GND_B12") (pintype "passive"))
      (node (ref "USBC3") (pin "0") (pinfunction "0_0") (pintype "passive"))
      (node (ref "USBC3") (pin "A1") (pinfunction "GND_A1") (pintype "passive"))
      (node (ref "USBC3") (pin "A12") (pinfunction "GND_A12") (pintype "passive"))
      (node (ref "USBC3") (pin "B1") (pinfunction "GND_B1") (pintype "passive"))
      (node (ref "USBC3") (pin "B12") (pinfunction "GND_B12") (pintype "passive"))
      (node (ref "V1") (pin "1") (pinfunction "GND_1") (pintype "passive"))
    )
    (net (code "41") (name "Net-(C9-Pad1)") (class "Default")
      (node (ref "C9") (pin "1") (pinfunction "1_1") (pintype "passive"))
      (node (ref "L1") (pin "1") (pinfunction "1_1") (pintype "passive"))
      (node (ref "U2") (pin "14") (pinfunction "LX_14") (pintype "passive"))
      (node (ref "U2") (pin "15") (pinfunction "LX_15") (pintype "passive"))
      (node (ref "U2") (pin "16") (pinfunction "LX_16") (pintype "passive"))
      (node (ref "U2") (pin "17") (pinfunction "LX_17") (pintype "passive"))
      (node (ref "U2") (pin "18") (pinfunction "LX_18") (pintype "passive"))
    )
    (net (code "42") (name "Net-(CP1-VDD)") (class "Default")
      (node (ref "C30") (pin "1") (pinfunction "1_1") (pintype "passive"))
      (node (ref "CP1") (pin "6") (pinfunction "VDD_6") (pintype "power_in"))
    )
    (net (code "43") (name "Net-(D1-A)") (class "Default")
      (node (ref "D1") (pin "1") (pinfunction "A_1") (pintype "passive"))
      (node (ref "USBC1") (pin "A4") (pinfunction "VBUS_A4") (pintype "passive"))
      (node (ref "USBC1") (pin "A9") (pinfunction "VBUS_A9") (pintype "passive"))
      (node (ref "USBC1") (pin "B4") (pinfunction "VBUS_B4") (pintype "passive"))
      (node (ref "USBC1") (pin "B9") (pinfunction "VBUS_B9") (pintype "passive"))
    )
    (net (code "44") (name "Net-(LED1-A)") (class "Default")
      (node (ref "LED1") (pin "1") (pinfunction "A_1") (pintype "passive"))
      (node (ref "R4") (pin "2") (pinfunction "2_2") (pintype "passive"))
    )
    (net (code "45") (name "Net-(LED2-A)") (class "Default")
      (node (ref "LED2") (pin "1") (pinfunction "A_1") (pintype "passive"))
      (node (ref "LED3") (pin "2") (pinfunction "K_2") (pintype "passive"))
      (node (ref "R22") (pin "1") (pinfunction "1_1") (pintype "passive"))
    )
    (net (code "46") (name "Net-(LED2-K)") (class "Default")
      (node (ref "LED2") (pin "2") (pinfunction "K_2") (pintype "passive"))
      (node (ref "LED3") (pin "1") (pinfunction "A_1") (pintype "passive"))
      (node (ref "LED4") (pin "2") (pinfunction "K_2") (pintype "passive"))
      (node (ref "LED5") (pin "1") (pinfunction "A_1") (pintype "passive"))
      (node (ref "R23") (pin "2") (pinfunction "2_2") (pintype "passive"))
      (node (ref "U2") (pin "13") (pinfunction "L3_13") (pintype "passive"))
    )
    (net (code "47") (name "Net-(LED4-A)") (class "Default")
      (node (ref "LED4") (pin "1") (pinfunction "A_1") (pintype "passive"))
      (node (ref "LED5") (pin "2") (pinfunction "K_2") (pintype "passive"))
      (node (ref "R21") (pin "1") (pinfunction "1_1") (pintype "passive"))
    )
    (net (code "48") (name "Net-(LED6-A)") (class "Default")
      (node (ref "LED6") (pin "1") (pinfunction "A_1") (pintype "passive"))
      (node (ref "R26") (pin "2") (pinfunction "2_2") (pintype "passive"))
    )
    (net (code "49") (name "Net-(LED7-A)") (class "Default")
      (node (ref "LED7") (pin "1") (pinfunction "A_1") (pintype "passive"))
      (node (ref "R27") (pin "2") (pinfunction "2_2") (pintype "passive"))
    )
    (net (code "50") (name "Net-(LED8-A)") (class "Default")
      (node (ref "LED8") (pin "1") (pinfunction "A_1") (pintype "passive"))
      (node (ref "R10") (pin "1") (pinfunction "1_1") (pintype "passive"))
    )
    (net (code "51") (name "Net-(LED10-A)") (class "Default")
      (node (ref "LED10") (pin "1") (pinfunction "A_1") (pintype "passive"))
      (node (ref "LED11") (pin "1") (pinfunction "A_1") (pintype "passive"))
      (node (ref "LED9") (pin "1") (pinfunction "A_1") (pintype "passive"))
      (node (ref "R9") (pin "2") (pinfunction "2_2") (pintype "passive"))
    )
    (net (code "52") (name "Net-(R28-Pad2)") (class "Default")
      (node (ref "R28") (pin "2") (pinfunction "2_2") (pintype "passive"))
      (node (ref "SW1") (pin "1") (pinfunction "1_1") (pintype "passive"))
    )
    (net (code "53") (name "Net-(U1A-BOOT0)") (class "Default")
      (node (ref "R2") (pin "1") (pinfunction "1_1") (pintype "passive"))
      (node (ref "U1") (pin "44") (pinfunction "BOOT0_44") (pintype "input"))
    )
    (net (code "54") (name "Net-(U1A-PB2)") (class "Default")
      (node (ref "R1") (pin "1") (pinfunction "1_1") (pintype "passive"))
      (node (ref "U1") (pin "20") (pinfunction "PB2_20") (pintype "bidirectional"))
    )
    (net (code "55") (name "Net-(U1A-PD0-OSC_IN)") (class "Default")
      (node (ref "C7") (pin "2") (pinfunction "2_2") (pintype "passive"))
      (node (ref "U1") (pin "5") (pinfunction "PD0-OSC_IN_5") (pintype "bidirectional"))
      (node (ref "X1") (pin "2") (pinfunction "2_2") (pintype "passive"))
    )
    (net (code "56") (name "Net-(U1A-PD1)") (class "Default")
      (node (ref "C8") (pin "2") (pinfunction "2_2") (pintype "passive"))
      (node (ref "U1") (pin "6") (pinfunction "PD1_6") (pintype "bidirectional"))
      (node (ref "X1") (pin "1") (pinfunction "1_1") (pintype "passive"))
    )
    (net (code "57") (name "Net-(U2-L1)") (class "Default")
      (node (ref "R21") (pin "2") (pinfunction "2_2") (pintype "passive"))
      (node (ref "U2") (pin "11") (pinfunction "L1_11") (pintype "passive"))
    )
    (net (code "58") (name "Net-(U2-L2)") (class "Default")
      (node (ref "R22") (pin "2") (pinfunction "2_2") (pintype "passive"))
      (node (ref "U2") (pin "12") (pinfunction "L2_12") (pintype "passive"))
    )
    (net (code "59") (name "Net-(U2-NTC)") (class "Default")
      (node (ref "R24") (pin "1") (pinfunction "1_1") (pintype "passive"))
      (node (ref "R25") (pin "1") (pinfunction "1_1") (pintype "passive"))
      (node (ref "U2") (pin "10") (pinfunction "NTC_10") (pintype "passive"))
    )
    (net (code "60") (name "Net-(USBC1-CC1)") (class "Default")
      (node (ref "R13") (pin "2") (pinfunction "2_2") (pintype "passive"))
      (node (ref "USBC1") (pin "A5") (pinfunction "CC1_A5") (pintype "passive"))
    )
    (net (code "61") (name "Net-(USBC1-CC2)") (class "Default")
      (node (ref "R12") (pin "1") (pinfunction "1_1") (pintype "passive"))
      (node (ref "USBC1") (pin "B5") (pinfunction "CC2_B5") (pintype "passive"))
    )
    (net (code "62") (name "Net-(USBC3-CC1)") (class "Default")
      (node (ref "R31") (pin "2") (pinfunction "2_2") (pintype "passive"))
      (node (ref "USBC3") (pin "A5") (pinfunction "CC1_A5") (pintype "passive"))
    )
    (net (code "63") (name "Net-(USBC3-CC2)") (class "Default")
      (node (ref "R30") (pin "1") (pinfunction "1_1") (pintype "passive"))
      (node (ref "USBC3") (pin "B5") (pinfunction "CC2_B5") (pintype "passive"))
    )
    (net (code "64") (name "unconnected-(CP1-CTS-Pad23)") (class "Default")
      (node (ref "CP1") (pin "23") (pinfunction "CTS_23") (pintype "passive+no_connect"))
    )
    (net (code "65") (name "unconnected-(CP1-DCD-Pad1)") (class "Default")
      (node (ref "CP1") (pin "1") (pinfunction "DCD_1") (pintype "passive+no_connect"))
    )
    (net (code "66") (name "unconnected-(CP1-DTR-Pad28)") (class "Default")
      (node (ref "CP1") (pin "28") (pinfunction "DTR_28") (pintype "passive+no_connect"))
    )
    (net (code "67") (name "unconnected-(CP1-NC-Pad10)") (class "Default")
      (node (ref "CP1") (pin "10") (pinfunction "NC_10") (pintype "passive+no_connect"))
    )
    (net (code "68") (name "unconnected-(CP1-NC-Pad13)") (class "Default")
      (node (ref "CP1") (pin "13") (pinfunction "NC_13") (pintype "passive+no_connect"))
    )
    (net (code "69") (name "unconnected-(CP1-NC-Pad14)") (class "Default")
      (node (ref "CP1") (pin "14") (pinfunction "NC_14") (pintype "passive+no_connect"))
    )
    (net (code "70") (name "unconnected-(CP1-NC-Pad15)") (class "Default")
      (node (ref "CP1") (pin "15") (pinfunction "NC_15") (pintype "passive+no_connect"))
    )
    (net (code "71") (name "unconnected-(CP1-NC-Pad16)") (class "Default")
      (node (ref "CP1") (pin "16") (pinfunction "NC_16") (pintype "passive+no_connect"))
    )
    (net (code "72") (name "unconnected-(CP1-NC-Pad17)") (class "Default")
      (node (ref "CP1") (pin "17") (pinfunction "NC_17") (pintype "passive+no_connect"))
    )
    (net (code "73") (name "unconnected-(CP1-NC-Pad18)") (class "Default")
      (node (ref "CP1") (pin "18") (pinfunction "NC_18") (pintype "passive+no_connect"))
    )
    (net (code "74") (name "unconnected-(CP1-NC-Pad19)") (class "Default")
      (node (ref "CP1") (pin "19") (pinfunction "NC_19") (pintype "passive+no_connect"))
    )
    (net (code "75") (name "unconnected-(CP1-NC-Pad20)") (class "Default")
      (node (ref "CP1") (pin "20") (pinfunction "NC_20") (pintype "passive+no_connect"))
    )
    (net (code "76") (name "unconnected-(CP1-NC-Pad21)") (class "Default")
      (node (ref "CP1") (pin "21") (pinfunction "NC_21") (pintype "passive+no_connect"))
    )
    (net (code "77") (name "unconnected-(CP1-NC-Pad22)") (class "Default")
      (node (ref "CP1") (pin "22") (pinfunction "NC_22") (pintype "passive+no_connect"))
    )
    (net (code "78") (name "unconnected-(CP1-RI-Pad2)") (class "Default")
      (node (ref "CP1") (pin "2") (pinfunction "RI_2") (pintype "passive+no_connect"))
    )
    (net (code "79") (name "unconnected-(CP1-RST#-Pad9)") (class "Default")
      (node (ref "CP1") (pin "9") (pinfunction "RST#_9") (pintype "bidirectional+no_connect"))
    )
    (net (code "80") (name "unconnected-(CP1-RTS-Pad24)") (class "Default")
      (node (ref "CP1") (pin "24") (pinfunction "RTS_24") (pintype "passive+no_connect"))
    )
    (net (code "81") (name "unconnected-(CP1-SDR-Pad27)") (class "Default")
      (node (ref "CP1") (pin "27") (pinfunction "SDR_27") (pintype "passive+no_connect"))
    )
    (net (code "82") (name "unconnected-(CP1-SUSPEND#-Pad11)") (class "Default")
      (node (ref "CP1") (pin "11") (pinfunction "SUSPEND#_11") (pintype "passive+no_connect"))
    )
    (net (code "83") (name "unconnected-(CP1-SUSPEND-Pad12)") (class "Default")
      (node (ref "CP1") (pin "12") (pinfunction "SUSPEND_12") (pintype "passive+no_connect"))
    )
    (net (code "84") (name "unconnected-(JP8-Pad2)") (class "Default")
      (node (ref "JP8") (pin "2") (pinfunction "2_2") (pintype "passive"))
    )
    (net (code "85") (name "unconnected-(U1A-PA0-WKUP-Pad10)") (class "Default")
      (node (ref "U1") (pin "10") (pinfunction "PA0-WKUP_10") (pintype "bidirectional+no_connect"))
    )
    (net (code "86") (name "unconnected-(U1A-PA1-Pad11)") (class "Default")
      (node (ref "U1") (pin "11") (pinfunction "PA1_11") (pintype "bidirectional+no_connect"))
    )
    (net (code "87") (name "unconnected-(U1A-PA4-Pad14)") (class "Default")
      (node (ref "U1") (pin "14") (pinfunction "PA4_14") (pintype "bidirectional+no_connect"))
    )
    (net (code "88") (name "unconnected-(U1A-PA5-Pad15)") (class "Default")
      (node (ref "U1") (pin "15") (pinfunction "PA5_15") (pintype "bidirectional+no_connect"))
    )
    (net (code "89") (name "unconnected-(U1A-PA6-Pad16)") (class "Default")
      (node (ref "U1") (pin "16") (pinfunction "PA6_16") (pintype "bidirectional+no_connect"))
    )
    (net (code "90") (name "unconnected-(U1A-PA7-Pad17)") (class "Default")
      (node (ref "U1") (pin "17") (pinfunction "PA7_17") (pintype "bidirectional+no_connect"))
    )
    (net (code "91") (name "unconnected-(U1A-PA8-Pad29)") (class "Default")
      (node (ref "U1") (pin "29") (pinfunction "PA8_29") (pintype "bidirectional+no_connect"))
    )
    (net (code "92") (name "unconnected-(U1A-PA9-Pad30)") (class "Default")
      (node (ref "U1") (pin "30") (pinfunction "PA9_30") (pintype "bidirectional+no_connect"))
    )
    (net (code "93") (name "unconnected-(U1A-PA10-Pad31)") (class "Default")
      (node (ref "U1") (pin "31") (pinfunction "PA10_31") (pintype "bidirectional+no_connect"))
    )
    (net (code "94") (name "unconnected-(U1A-PA15-Pad38)") (class "Default")
      (node (ref "U1") (pin "38") (pinfunction "PA15_38") (pintype "bidirectional+no_connect"))
    )
    (net (code "95") (name "unconnected-(U1A-PB0-Pad18)") (class "Default")
      (node (ref "U1") (pin "18") (pinfunction "PB0_18") (pintype "bidirectional+no_connect"))
    )
    (net (code "96") (name "unconnected-(U1A-PB1-Pad19)") (class "Default")
      (node (ref "U1") (pin "19") (pinfunction "PB1_19") (pintype "bidirectional+no_connect"))
    )
    (net (code "97") (name "unconnected-(U1A-PB3-Pad39)") (class "Default")
      (node (ref "U1") (pin "39") (pinfunction "PB3_39") (pintype "bidirectional+no_connect"))
    )
    (net (code "98") (name "unconnected-(U1A-PB5-Pad41)") (class "Default")
      (node (ref "U1") (pin "41") (pinfunction "PB5_41") (pintype "bidirectional+no_connect"))
    )
    (net (code "99") (name "unconnected-(U1A-PB6-Pad42)") (class "Default")
      (node (ref "U1") (pin "42") (pinfunction "PB6_42") (pintype "bidirectional+no_connect"))
    )
    (net (code "100") (name "unconnected-(U1A-PB7-Pad43)") (class "Default")
      (node (ref "U1") (pin "43") (pinfunction "PB7_43") (pintype "bidirectional+no_connect"))
    )
    (net (code "101") (name "unconnected-(U1A-PB8-Pad45)") (class "Default")
      (node (ref "U1") (pin "45") (pinfunction "PB8_45") (pintype "bidirectional+no_connect"))
    )
    (net (code "102") (name "unconnected-(U1A-PB9-Pad46)") (class "Default")
      (node (ref "U1") (pin "46") (pinfunction "PB9_46") (pintype "bidirectional"))
    )
    (net (code "103") (name "unconnected-(U1A-PB10-Pad21)") (class "Default")
      (node (ref "U1") (pin "21") (pinfunction "PB10_21") (pintype "bidirectional+no_connect"))
    )
    (net (code "104") (name "unconnected-(U1A-PB11-Pad22)") (class "Default")
      (node (ref "U1") (pin "22") (pinfunction "PB11_22") (pintype "bidirectional+no_connect"))
    )
    (net (code "105") (name "unconnected-(U1A-PB12-Pad25)") (class "Default")
      (node (ref "U1") (pin "25") (pinfunction "PB12_25") (pintype "bidirectional+no_connect"))
    )
    (net (code "106") (name "unconnected-(U1A-PB15-Pad28)") (class "Default")
      (node (ref "U1") (pin "28") (pinfunction "PB15_28") (pintype "bidirectional+no_connect"))
    )
    (net (code "107") (name "unconnected-(U1A-PC13-TAMPER-RTC-Pad2)") (class "Default")
      (node (ref "U1") (pin "2") (pinfunction "PC13-TAMPER-RTC_2") (pintype "bidirectional+no_connect"))
    )
    (net (code "108") (name "unconnected-(U1A-PC14-OSC32_IN-Pad3)") (class "Default")
      (node (ref "U1") (pin "3") (pinfunction "PC14-OSC32_IN_3") (pintype "bidirectional+no_connect"))
    )
    (net (code "109") (name "unconnected-(U1A-PC15-OSC32_OUT-Pad4)") (class "Default")
      (node (ref "U1") (pin "4") (pinfunction "PC15-OSC32_OUT_4") (pintype "bidirectional+no_connect"))
    )
    (net (code "110") (name "unconnected-(U2-DMA1-Pad38)") (class "Default")
      (node (ref "U2") (pin "38") (pinfunction "DMA1_38") (pintype "bidirectional+no_connect"))
    )
    (net (code "111") (name "unconnected-(U2-DMA2-Pad40)") (class "Default")
      (node (ref "U2") (pin "40") (pinfunction "DMA2_40") (pintype "bidirectional+no_connect"))
    )
    (net (code "112") (name "unconnected-(U2-DPA1-Pad39)") (class "Default")
      (node (ref "U2") (pin "39") (pinfunction "DPA1_39") (pintype "bidirectional+no_connect"))
    )
    (net (code "113") (name "unconnected-(U2-DPA2-Pad1)") (class "Default")
      (node (ref "U2") (pin "1") (pinfunction "DPA2_1") (pintype "bidirectional+no_connect"))
    )
    (net (code "114") (name "unconnected-(U2-VIN-Pad30)") (class "Default")
      (node (ref "U2") (pin "30") (pinfunction "VIN_30") (pintype "passive+no_connect"))
    )
    (net (code "115") (name "unconnected-(U2-VING-Pad31)") (class "Default")
      (node (ref "U2") (pin "31") (pinfunction "VING_31") (pintype "passive+no_connect"))
    )
    (net (code "116") (name "unconnected-(USBC1-SBU1-PadA8)") (class "Default")
      (node (ref "USBC1") (pin "A8") (pinfunction "SBU1_A8") (pintype "passive+no_connect"))
    )
    (net (code "117") (name "unconnected-(USBC1-SBU2-PadB8)") (class "Default")
      (node (ref "USBC1") (pin "B8") (pinfunction "SBU2_B8") (pintype "passive+no_connect"))
    )
    (net (code "118") (name "unconnected-(USBC2-SBU1-PadA8)") (class "Default")
      (node (ref "USBC2") (pin "A8") (pinfunction "SBU1_A8") (pintype "passive+no_connect"))
    )
    (net (code "119") (name "unconnected-(USBC2-SBU2-PadB8)") (class "Default")
      (node (ref "USBC2") (pin "B8") (pinfunction "SBU2_B8") (pintype "passive+no_connect"))
    )
    (net (code "120") (name "unconnected-(USBC3-SBU1-PadA8)") (class "Default")
      (node (ref "USBC3") (pin "A8") (pinfunction "SBU1_A8") (pintype "passive+no_connect"))
    )
    (net (code "121") (name "unconnected-(USBC3-SBU2-PadB8)") (class "Default")
      (node (ref "USBC3") (pin "B8") (pinfunction "SBU2_B8") (pintype "passive+no_connect"))
    )
  )
)
